# GL3520_4_Ports.net
KiCad netlist of a schematic drawn in Altium Designer
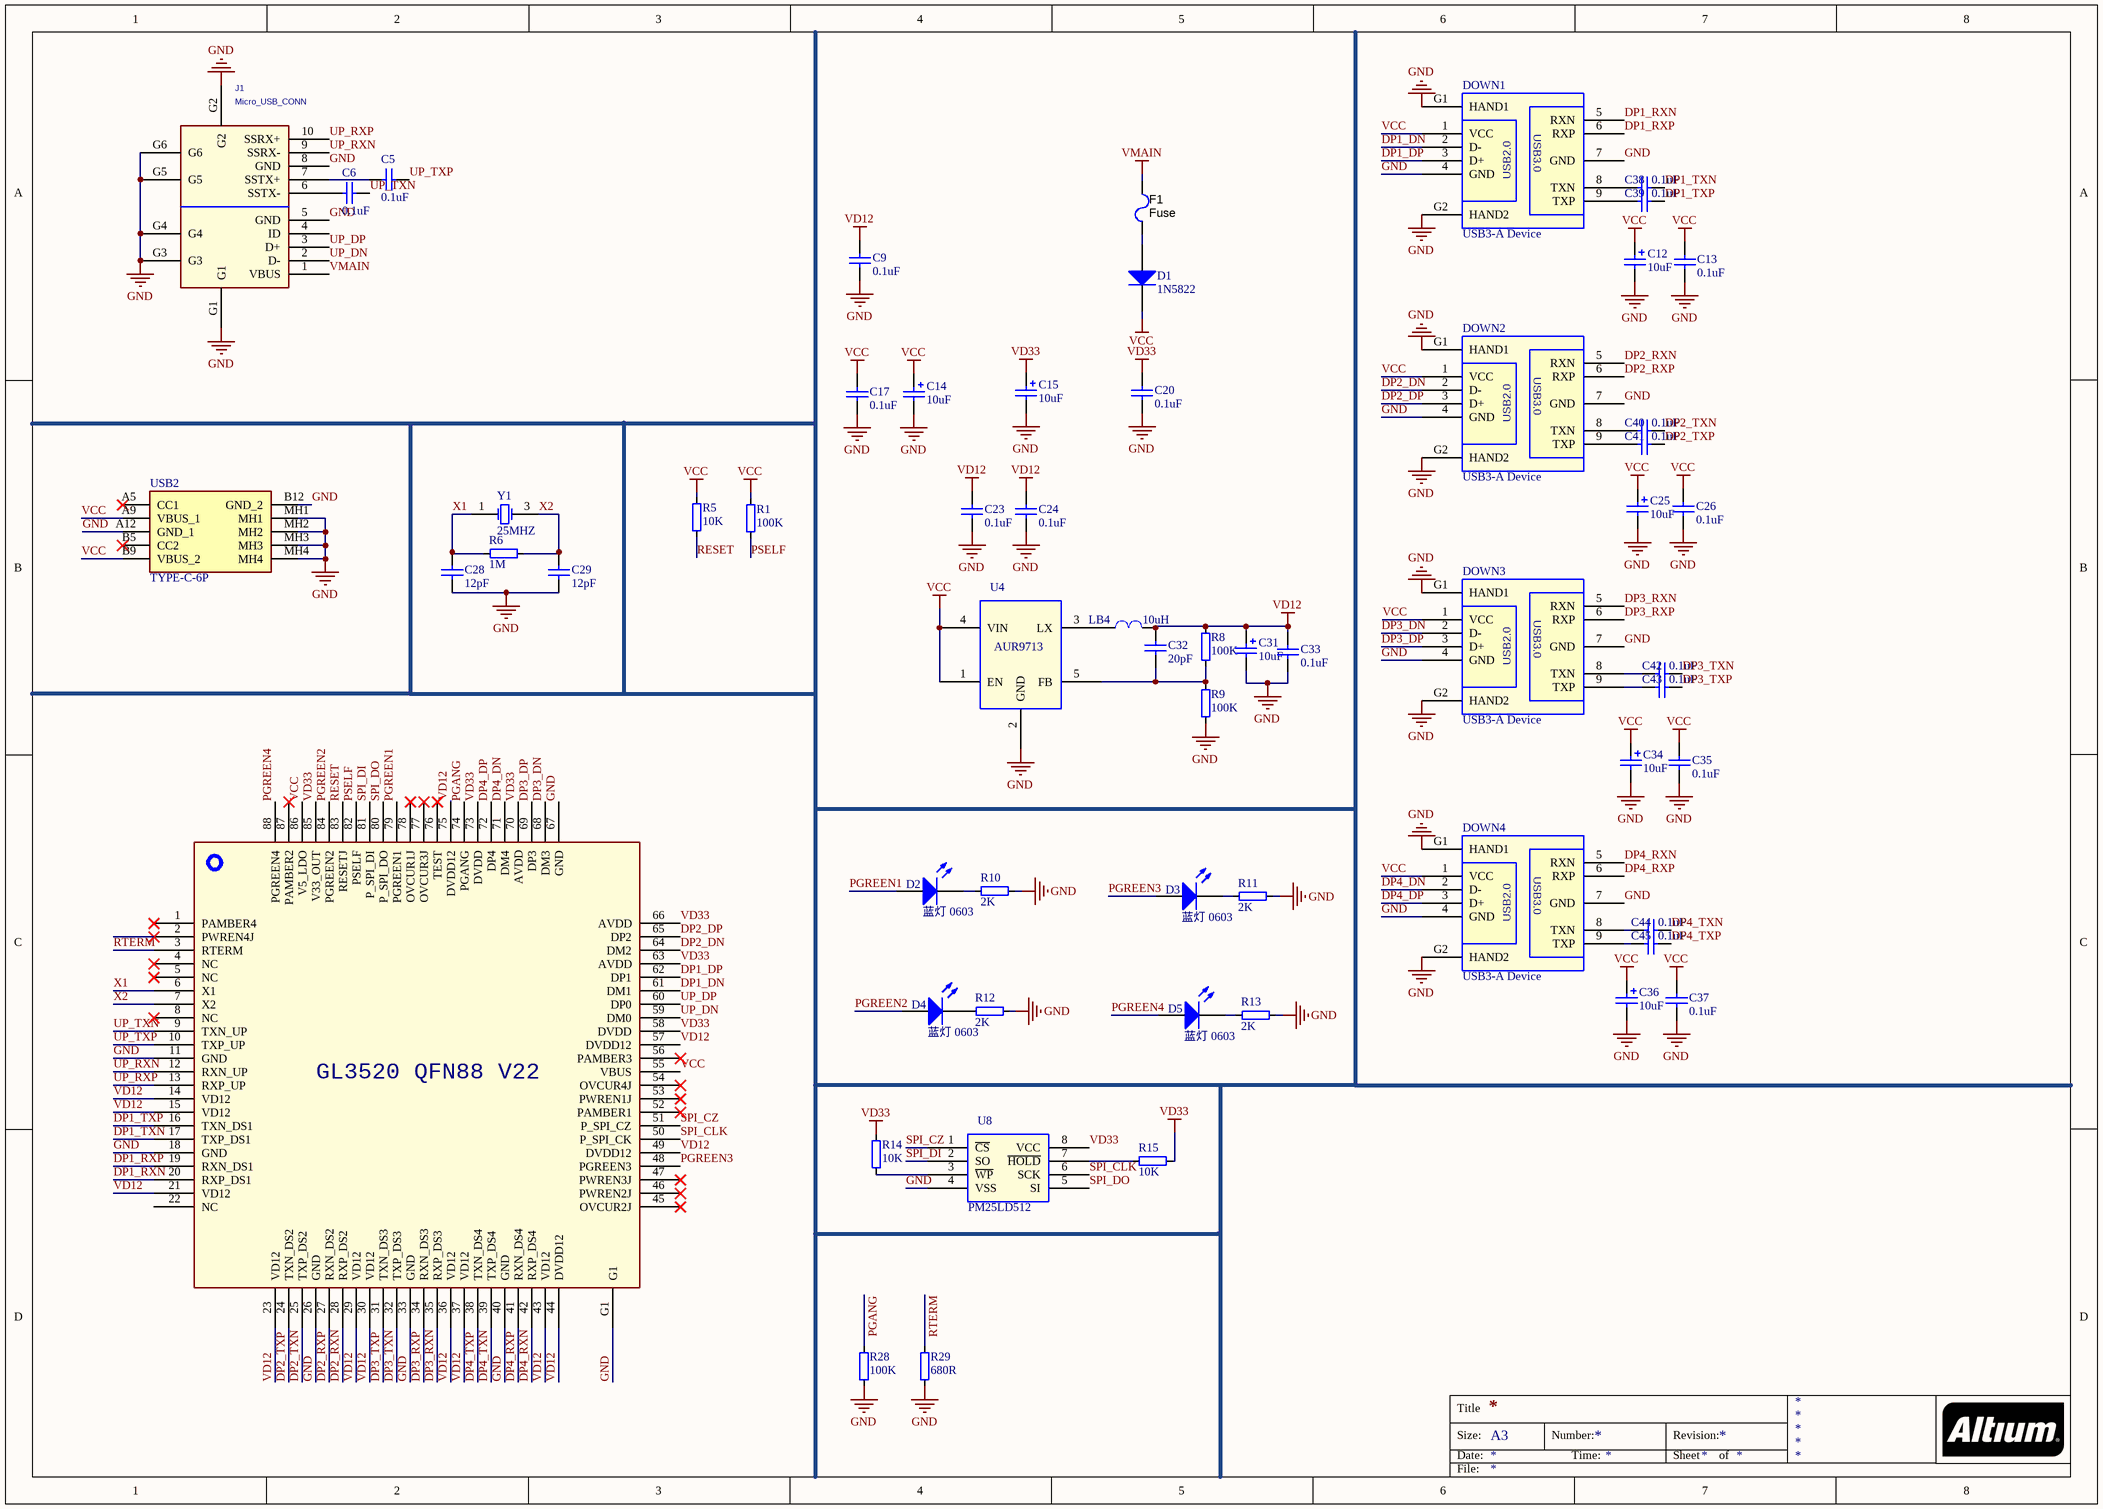
[diagram p0: GL3520 4 Ports.SchDoc]

(export (version "E")
  (design (tool "Eeschema 10.0.6"))
  (components
    (comp (ref "C5")
      (value "0.1uF")
      (footprint "C 0603_L")
      (description "贴片电容")
      (libsource (lib "嘉立创") (part "0603 2.2uF (225) 10% 16V"))
    )
    (comp (ref "C6")
      (value "0.1uF")
      (footprint "C 0603_L")
      (description "贴片电容")
      (libsource (lib "嘉立创") (part "0603 2.2uF (225) 10% 16V"))
    )
    (comp (ref "C9")
      (value "0.1uF")
      (footprint "C 0603_L")
      (description "贴片电容")
      (libsource (lib "嘉立创") (part "0603 2.2uF (225) 10% 16V"))
    )
    (comp (ref "C12")
      (value "10uF")
      (footprint "CASE-A_3216")
      (description "钽电容")
      (libsource (lib "嘉立创") (part "3216 10uF (106) 10% 16V"))
    )
    (comp (ref "C13")
      (value "0.1uF")
      (footprint "C 0603_L")
      (description "贴片电容")
      (libsource (lib "嘉立创") (part "0603 2.2uF (225) 10% 16V"))
    )
    (comp (ref "C14")
      (value "10uF")
      (footprint "CASE-A_3216")
      (description "钽电容1206")
      (libsource (lib "嘉立创") (part "3216 10uF (106) 10% 16V"))
    )
    (comp (ref "C15")
      (value "10uF")
      (footprint "CASE-A_3216")
      (description "钽电容1206")
      (libsource (lib "嘉立创") (part "3216 10uF (106) 10% 16V"))
    )
    (comp (ref "C17")
      (value "0.1uF")
      (footprint "C 0603_L")
      (description "贴片电容")
      (libsource (lib "嘉立创") (part "0603 2.2uF (225) 10% 16V"))
    )
    (comp (ref "C20")
      (value "0.1uF")
      (footprint "C 0603_L")
      (description "贴片电容")
      (libsource (lib "嘉立创") (part "0603 2.2uF (225) 10% 16V"))
    )
    (comp (ref "C23")
      (value "0.1uF")
      (footprint "C 0603_L")
      (description "贴片电容")
      (libsource (lib "嘉立创") (part "0603 2.2uF (225) 10% 16V"))
    )
    (comp (ref "C24")
      (value "0.1uF")
      (footprint "C 0603_L")
      (description "贴片电容")
      (libsource (lib "嘉立创") (part "0603 2.2uF (225) 10% 16V"))
    )
    (comp (ref "C25")
      (value "10uF")
      (footprint "CASE-A_3216")
      (description "钽电容")
      (libsource (lib "嘉立创") (part "3216 10uF (106) 10% 16V"))
    )
    (comp (ref "C26")
      (value "0.1uF")
      (footprint "C 0603_L")
      (description "贴片电容")
      (libsource (lib "嘉立创") (part "0603 2.2uF (225) 10% 16V"))
    )
    (comp (ref "C28")
      (value "12pF")
      (footprint "C 0603_L")
      (description "贴片电容")
      (libsource (lib "嘉立创") (part "0603 2.2uF (225) 10% 16V"))
    )
    (comp (ref "C29")
      (value "12pF")
      (footprint "C 0603_L")
      (description "贴片电容")
      (libsource (lib "嘉立创") (part "0603 2.2uF (225) 10% 16V"))
    )
    (comp (ref "C31")
      (value "10uF")
      (footprint "CASE-A_3216")
      (description "钽电容")
      (libsource (lib "嘉立创") (part "3216 10uF (106) 10% 16V"))
    )
    (comp (ref "C32")
      (value "20pF")
      (footprint "C 0603_L")
      (description "贴片电容")
      (libsource (lib "嘉立创") (part "0603 2.2uF (225) 10% 16V"))
    )
    (comp (ref "C33")
      (value "0.1uF")
      (footprint "C 0603_L")
      (description "贴片电容")
      (libsource (lib "嘉立创") (part "0603 2.2uF (225) 10% 16V"))
    )
    (comp (ref "C34")
      (value "10uF")
      (footprint "CASE-A_3216")
      (description "钽电容")
      (libsource (lib "嘉立创") (part "3216 10uF (106) 10% 16V"))
    )
    (comp (ref "C35")
      (value "0.1uF")
      (footprint "C 0603_L")
      (description "贴片电容")
      (libsource (lib "嘉立创") (part "0603 2.2uF (225) 10% 16V"))
    )
    (comp (ref "C36")
      (value "10uF")
      (footprint "CASE-A_3216")
      (description "钽电容")
      (libsource (lib "嘉立创") (part "3216 10uF (106) 10% 16V"))
    )
    (comp (ref "C37")
      (value "0.1uF")
      (footprint "C 0603_L")
      (description "贴片电容")
      (libsource (lib "嘉立创") (part "0603 2.2uF (225) 10% 16V"))
    )
    (comp (ref "C38")
      (value "0.1uF")
      (footprint "C 0603_L")
      (description "贴片电容")
      (libsource (lib "嘉立创") (part "0603 2.2uF (225) 10% 16V"))
    )
    (comp (ref "C39")
      (value "0.1uF")
      (footprint "C 0603_L")
      (description "贴片电容")
      (libsource (lib "嘉立创") (part "0603 2.2uF (225) 10% 16V"))
    )
    (comp (ref "C40")
      (value "0.1uF")
      (footprint "C 0603_L")
      (description "贴片电容")
      (libsource (lib "嘉立创") (part "0603 2.2uF (225) 10% 16V"))
    )
    (comp (ref "C41")
      (value "0.1uF")
      (footprint "C 0603_L")
      (description "贴片电容")
      (libsource (lib "嘉立创") (part "0603 2.2uF (225) 10% 16V"))
    )
    (comp (ref "C42")
      (value "0.1uF")
      (footprint "C 0603_L")
      (description "贴片电容")
      (libsource (lib "嘉立创") (part "0603 2.2uF (225) 10% 16V"))
    )
    (comp (ref "C43")
      (value "0.1uF")
      (footprint "C 0603_L")
      (description "贴片电容")
      (libsource (lib "嘉立创") (part "0603 2.2uF (225) 10% 16V"))
    )
    (comp (ref "C44")
      (value "0.1uF")
      (footprint "C 0603_L")
      (description "贴片电容")
      (libsource (lib "嘉立创") (part "0603 2.2uF (225) 10% 16V"))
    )
    (comp (ref "C45")
      (value "0.1uF")
      (footprint "C 0603_L")
      (description "贴片电容")
      (libsource (lib "嘉立创") (part "0603 2.2uF (225) 10% 16V"))
    )
    (comp (ref "D1")
      (value "1N5822")
      (footprint "SMA")
      (description "3 Amp General Purpose Rectifier")
      (fields (field (name "PUBLISHER") "Altium Limited"))
      (libsource (lib "Miscellaneous Devices") (part "Diode 1N5400"))
    )
    (comp (ref "D2")
      (value "蓝灯 0603")
      (footprint "0603_LED_S1")
      (description "发光二极管")
      (libsource (lib "嘉立创") (part "0603 蓝灯"))
    )
    (comp (ref "D3")
      (value "蓝灯 0603")
      (footprint "0603_LED_S1")
      (description "发光二极管")
      (libsource (lib "嘉立创") (part "0603 蓝灯"))
    )
    (comp (ref "D4")
      (value "蓝灯 0603")
      (footprint "0603_LED_S1")
      (description "发光二极管")
      (libsource (lib "嘉立创") (part "0603 蓝灯"))
    )
    (comp (ref "D5")
      (value "蓝灯 0603")
      (footprint "0603_LED_S1")
      (description "发光二极管")
      (libsource (lib "嘉立创") (part "0603 蓝灯"))
    )
    (comp (ref "DOWN1")
      (value "USB3-A Device")
      (footprint "USB3.0-2 - duplicate")
      (libsource (lib "*") (part "USB3-A_5"))
    )
    (comp (ref "DOWN2")
      (value "USB3-A Device")
      (footprint "USB3.0-2 - duplicate")
      (libsource (lib "*") (part "USB3-A_5"))
    )
    (comp (ref "DOWN3")
      (value "USB3-A Device")
      (footprint "USB3.0-2 - duplicate")
      (libsource (lib "*") (part "USB3-A_5"))
    )
    (comp (ref "DOWN4")
      (value "USB3-A Device")
      (footprint "USB3.0-2 - duplicate")
      (libsource (lib "*") (part "USB3-A_5"))
    )
    (comp (ref "F1")
      (value "Fuse")
      (footprint "FU 1206")
      (fields
        (field (name "PARTNUMBER") "NANOSMDC020F-2")
        (field (name "MANUFACTURER") "TE Connectivity")
        (field (name "PUBLISHER") "Texas Instruments")
        (field (name "SYMBOLCREATOR") "a0412235")
      )
      (libsource (lib "TUSB8041_USB_3.0_Hub") (part "Fuse"))
    )
    (comp (ref "J1") (value "Micro_USB_CONN") (libsource (lib "*") (part "USB-UEB11123-2JK1-4H_0")))
    (comp (ref "LB4") (value "10uH") (footprint "CD43") (libsource (lib "*") (part "L-0603")))
    (comp (ref "R1") (value "100K") (footprint "R 0603_L") (libsource (lib "Jlink OB") (part "RES")))
    (comp (ref "R5") (value "10K") (footprint "R 0603_L") (libsource (lib "Jlink OB") (part "RES")))
    (comp (ref "R6") (value "1M") (footprint "R 0603_L") (libsource (lib "Jlink OB") (part "RES")))
    (comp (ref "R8") (value "100K") (footprint "R 0603_L") (libsource (lib "Jlink OB") (part "RES")))
    (comp (ref "R9") (value "100K") (footprint "R 0603_L") (libsource (lib "Jlink OB") (part "RES")))
    (comp (ref "R10") (value "2K") (footprint "R 0603_L") (libsource (lib "Jlink OB") (part "RES")))
    (comp (ref "R11") (value "2K") (footprint "R 0603_L") (libsource (lib "Jlink OB") (part "RES")))
    (comp (ref "R12") (value "2K") (footprint "R 0603_L") (libsource (lib "Jlink OB") (part "RES")))
    (comp (ref "R13") (value "2K") (footprint "R 0603_L") (libsource (lib "Jlink OB") (part "RES")))
    (comp (ref "R14") (value "10K") (footprint "R 0603_L") (libsource (lib "Jlink OB") (part "RES")))
    (comp (ref "R15") (value "10K") (footprint "R 0603_L") (libsource (lib "Jlink OB") (part "RES")))
    (comp (ref "R28") (value "100K") (footprint "R 0603_L") (libsource (lib "Jlink OB") (part "RES")))
    (comp (ref "R29") (value "680R") (footprint "R 0603_L") (libsource (lib "Jlink OB") (part "RES")))
    (comp (ref "U4") (value "AUR9713") (footprint "SOT23-5L") (libsource (lib "*") (part "AUR9705_3")))
    (comp (ref "U6")
      (value "GL3520_QFN88_V094-1_22")
      (footprint "QFN88")
      (libsource (lib "GL3520 4 Ports") (part "GL3520_QFN88_V094-1_22"))
    )
    (comp (ref "U8") (value "PM25LD512") (footprint "SOP8_M") (libsource (lib "*") (part "CAT25C128/256")))
    (comp (ref "USB2")
      (value "TYPE-C-6P")
      (footprint "TYPE-C-SMD_TYPE-C-31-M-16 - duplicate")
      (description "Connector")
      (fields (field (name "MANUFACTURER_PART_NUMBER") "TYPE-C-31-M-17"))
      (libsource (lib "SamacSys") (part "TYPE-C-31-M-17"))
    )
    (comp (ref "Y1")
      (value "25MHZ")
      (footprint "OSC 3225-4P")
      (description "贴片晶振")
      (libsource (lib "嘉立创") (part "SMD-3225_4P  25MHZ 12PF 10PPM"))
    )
  )
  (nets
    (net (code "1") (name "/DP1_DN") (class "Default")
      (node (ref "DOWN1") (pin "2") (pinfunction "D-_2") (pintype "passive"))
      (node (ref "U6") (pin "61") (pinfunction "DM1_61") (pintype "passive"))
    )
    (net (code "2") (name "/DP1_DP") (class "Default")
      (node (ref "DOWN1") (pin "3") (pinfunction "D+_3") (pintype "passive"))
      (node (ref "U6") (pin "62") (pinfunction "DP1_62") (pintype "passive"))
    )
    (net (code "3") (name "/DP1_RXN") (class "Default")
      (node (ref "DOWN1") (pin "5") (pinfunction "RXN_5") (pintype "passive"))
      (node (ref "U6") (pin "20") (pinfunction "RXP_DS1_20") (pintype "passive"))
    )
    (net (code "4") (name "/DP1_RXP") (class "Default")
      (node (ref "DOWN1") (pin "6") (pinfunction "RXP_6") (pintype "passive"))
      (node (ref "U6") (pin "19") (pinfunction "RXN_DS1_19") (pintype "passive"))
    )
    (net (code "5") (name "/DP1_TXN") (class "Default")
      (node (ref "C38") (pin "1") (pinfunction "1_1") (pintype "passive"))
      (node (ref "U6") (pin "17") (pinfunction "TXP_DS1_17") (pintype "passive"))
    )
    (net (code "6") (name "/DP1_TXP") (class "Default")
      (node (ref "C39") (pin "1") (pinfunction "1_1") (pintype "passive"))
      (node (ref "U6") (pin "16") (pinfunction "TXN_DS1_16") (pintype "passive"))
    )
    (net (code "7") (name "/DP2_DN") (class "Default")
      (node (ref "DOWN2") (pin "2") (pinfunction "D-_2") (pintype "passive"))
      (node (ref "U6") (pin "64") (pinfunction "DM2_64") (pintype "passive"))
    )
    (net (code "8") (name "/DP2_DP") (class "Default")
      (node (ref "DOWN2") (pin "3") (pinfunction "D+_3") (pintype "passive"))
      (node (ref "U6") (pin "65") (pinfunction "DP2_65") (pintype "passive"))
    )
    (net (code "9") (name "/DP2_RXN") (class "Default")
      (node (ref "DOWN2") (pin "5") (pinfunction "RXN_5") (pintype "passive"))
      (node (ref "U6") (pin "28") (pinfunction "RXP_DS2_28") (pintype "passive"))
    )
    (net (code "10") (name "/DP2_RXP") (class "Default")
      (node (ref "DOWN2") (pin "6") (pinfunction "RXP_6") (pintype "passive"))
      (node (ref "U6") (pin "27") (pinfunction "RXN_DS2_27") (pintype "passive"))
    )
    (net (code "11") (name "/DP2_TXN") (class "Default")
      (node (ref "C40") (pin "1") (pinfunction "1_1") (pintype "passive"))
      (node (ref "U6") (pin "25") (pinfunction "TXP_DS2_25") (pintype "passive"))
    )
    (net (code "12") (name "/DP2_TXP") (class "Default")
      (node (ref "C41") (pin "1") (pinfunction "1_1") (pintype "passive"))
      (node (ref "U6") (pin "24") (pinfunction "TXN_DS2_24") (pintype "passive"))
    )
    (net (code "13") (name "/DP3_DN") (class "Default")
      (node (ref "DOWN3") (pin "2") (pinfunction "D-_2") (pintype "passive"))
      (node (ref "U6") (pin "68") (pinfunction "DM3_68") (pintype "passive"))
    )
    (net (code "14") (name "/DP3_DP") (class "Default")
      (node (ref "DOWN3") (pin "3") (pinfunction "D+_3") (pintype "passive"))
      (node (ref "U6") (pin "69") (pinfunction "DP3_69") (pintype "passive"))
    )
    (net (code "15") (name "/DP3_RXN") (class "Default")
      (node (ref "DOWN3") (pin "5") (pinfunction "RXN_5") (pintype "passive"))
      (node (ref "U6") (pin "35") (pinfunction "RXP_DS3_35") (pintype "passive"))
    )
    (net (code "16") (name "/DP3_RXP") (class "Default")
      (node (ref "DOWN3") (pin "6") (pinfunction "RXP_6") (pintype "passive"))
      (node (ref "U6") (pin "34") (pinfunction "RXN_DS3_34") (pintype "passive"))
    )
    (net (code "17") (name "/DP3_TXN") (class "Default")
      (node (ref "C42") (pin "1") (pinfunction "1_1") (pintype "passive"))
      (node (ref "U6") (pin "32") (pinfunction "TXP_DS3_32") (pintype "passive"))
    )
    (net (code "18") (name "/DP3_TXP") (class "Default")
      (node (ref "C43") (pin "1") (pinfunction "1_1") (pintype "passive"))
      (node (ref "U6") (pin "31") (pinfunction "TXN_DS3_31") (pintype "passive"))
    )
    (net (code "19") (name "/DP4_DN") (class "Default")
      (node (ref "DOWN4") (pin "2") (pinfunction "D-_2") (pintype "passive"))
      (node (ref "U6") (pin "71") (pinfunction "DM4_71") (pintype "passive"))
    )
    (net (code "20") (name "/DP4_DP") (class "Default")
      (node (ref "DOWN4") (pin "3") (pinfunction "D+_3") (pintype "passive"))
      (node (ref "U6") (pin "72") (pinfunction "DP4_72") (pintype "passive"))
    )
    (net (code "21") (name "/DP4_RXN") (class "Default")
      (node (ref "DOWN4") (pin "5") (pinfunction "RXN_5") (pintype "passive"))
      (node (ref "U6") (pin "42") (pinfunction "RXP_DS4_42") (pintype "passive"))
    )
    (net (code "22") (name "/DP4_RXP") (class "Default")
      (node (ref "DOWN4") (pin "6") (pinfunction "RXP_6") (pintype "passive"))
      (node (ref "U6") (pin "41") (pinfunction "RXN_DS4_41") (pintype "passive"))
    )
    (net (code "23") (name "/DP4_TXN") (class "Default")
      (node (ref "C44") (pin "1") (pinfunction "1_1") (pintype "passive"))
      (node (ref "U6") (pin "39") (pinfunction "TXP_DS4_39") (pintype "passive"))
    )
    (net (code "24") (name "/DP4_TXP") (class "Default")
      (node (ref "C45") (pin "1") (pinfunction "1_1") (pintype "passive"))
      (node (ref "U6") (pin "38") (pinfunction "TXN_DS4_38") (pintype "passive"))
    )
    (net (code "25") (name "/PGANG") (class "Default")
      (node (ref "R28") (pin "1") (pinfunction "1_1") (pintype "passive"))
      (node (ref "U6") (pin "74") (pinfunction "PGANG_74") (pintype "passive"))
    )
    (net (code "26") (name "/PGREEN1") (class "Default")
      (node (ref "D2") (pin "A") (pinfunction "A_A") (pintype "passive"))
      (node (ref "U6") (pin "79") (pinfunction "PGREEN1_79") (pintype "passive"))
    )
    (net (code "27") (name "/PGREEN2") (class "Default")
      (node (ref "D4") (pin "A") (pinfunction "A_A") (pintype "passive"))
      (node (ref "U6") (pin "84") (pinfunction "PGREEN2_84") (pintype "passive"))
    )
    (net (code "28") (name "/PGREEN3") (class "Default")
      (node (ref "D3") (pin "A") (pinfunction "A_A") (pintype "passive"))
      (node (ref "U6") (pin "48") (pinfunction "PGREEN3_48") (pintype "passive"))
    )
    (net (code "29") (name "/PGREEN4") (class "Default")
      (node (ref "D5") (pin "A") (pinfunction "A_A") (pintype "passive"))
      (node (ref "U6") (pin "88") (pinfunction "PGREEN4_88") (pintype "passive"))
    )
    (net (code "30") (name "/PSELF") (class "Default")
      (node (ref "R1") (pin "2") (pinfunction "2_2") (pintype "passive"))
      (node (ref "U6") (pin "82") (pinfunction "PSELF_82") (pintype "passive"))
    )
    (net (code "31") (name "/RESET") (class "Default")
      (node (ref "R5") (pin "1") (pinfunction "1_1") (pintype "passive"))
      (node (ref "U6") (pin "83") (pinfunction "RESETJ_83") (pintype "passive"))
    )
    (net (code "32") (name "/RTERM") (class "Default")
      (node (ref "R29") (pin "1") (pinfunction "1_1") (pintype "passive"))
      (node (ref "U6") (pin "3") (pinfunction "RTERM_3") (pintype "passive"))
    )
    (net (code "33") (name "/SPI_CLK") (class "Default")
      (node (ref "U6") (pin "50") (pinfunction "P_SPI_CK_50") (pintype "passive"))
      (node (ref "U8") (pin "6") (pinfunction "SCK_6") (pintype "passive"))
    )
    (net (code "34") (name "/SPI_CZ") (class "Default")
      (node (ref "U6") (pin "51") (pinfunction "P_SPI_CZ_51") (pintype "passive"))
      (node (ref "U8") (pin "1") (pinfunction "~{CS}_1") (pintype "passive"))
    )
    (net (code "35") (name "/SPI_DI") (class "Default")
      (node (ref "U6") (pin "81") (pinfunction "P_SPI_DI_81") (pintype "passive"))
      (node (ref "U8") (pin "2") (pinfunction "SO_2") (pintype "passive"))
    )
    (net (code "36") (name "/SPI_DO") (class "Default")
      (node (ref "U6") (pin "80") (pinfunction "P_SPI_DO_80") (pintype "passive"))
      (node (ref "U8") (pin "5") (pinfunction "SI_5") (pintype "passive"))
    )
    (net (code "37") (name "/UP_DN") (class "Default")
      (node (ref "J1") (pin "2") (pinfunction "D-_2") (pintype "passive"))
      (node (ref "U6") (pin "59") (pinfunction "DM0_59") (pintype "passive"))
    )
    (net (code "38") (name "/UP_DP") (class "Default")
      (node (ref "J1") (pin "3") (pinfunction "D+_3") (pintype "passive"))
      (node (ref "U6") (pin "60") (pinfunction "DP0_60") (pintype "passive"))
    )
    (net (code "39") (name "/UP_RXN") (class "Default")
      (node (ref "J1") (pin "9") (pinfunction "SSRX-_9") (pintype "passive"))
      (node (ref "U6") (pin "12") (pinfunction "RXN_UP_12") (pintype "passive"))
    )
    (net (code "40") (name "/UP_RXP") (class "Default")
      (node (ref "J1") (pin "10") (pinfunction "SSRX+_10") (pintype "passive"))
      (node (ref "U6") (pin "13") (pinfunction "RXP_UP_13") (pintype "passive"))
    )
    (net (code "41") (name "/UP_TXN") (class "Default")
      (node (ref "C6") (pin "1") (pinfunction "1_1") (pintype "passive"))
      (node (ref "U6") (pin "9") (pinfunction "TXN_UP_9") (pintype "passive"))
    )
    (net (code "42") (name "/UP_TXP") (class "Default")
      (node (ref "C5") (pin "1") (pinfunction "1_1") (pintype "passive"))
      (node (ref "U6") (pin "10") (pinfunction "TXP_UP_10") (pintype "passive"))
    )
    (net (code "43") (name "/X1") (class "Default")
      (node (ref "C28") (pin "2") (pinfunction "2_2") (pintype "passive"))
      (node (ref "R6") (pin "1") (pinfunction "1_1") (pintype "passive"))
      (node (ref "U6") (pin "6") (pinfunction "X1_6") (pintype "passive"))
      (node (ref "Y1") (pin "1") (pinfunction "OSC1_1") (pintype "passive"))
    )
    (net (code "44") (name "/X2") (class "Default")
      (node (ref "C29") (pin "2") (pinfunction "2_2") (pintype "passive"))
      (node (ref "R6") (pin "2") (pinfunction "2_2") (pintype "passive"))
      (node (ref "U6") (pin "7") (pinfunction "X2_7") (pintype "passive"))
      (node (ref "Y1") (pin "3") (pinfunction "OSC2_3") (pintype "passive"))
    )
    (net (code "45") (name "GND") (class "Default")
      (node (ref "C12") (pin "2") (pinfunction "2_2") (pintype "passive"))
      (node (ref "C13") (pin "1") (pinfunction "1_1") (pintype "passive"))
      (node (ref "C14") (pin "2") (pinfunction "2_2") (pintype "passive"))
      (node (ref "C15") (pin "2") (pinfunction "2_2") (pintype "passive"))
      (node (ref "C17") (pin "1") (pinfunction "1_1") (pintype "passive"))
      (node (ref "C20") (pin "1") (pinfunction "1_1") (pintype "passive"))
      (node (ref "C23") (pin "1") (pinfunction "1_1") (pintype "passive"))
      (node (ref "C24") (pin "1") (pinfunction "1_1") (pintype "passive"))
      (node (ref "C25") (pin "2") (pinfunction "2_2") (pintype "passive"))
      (node (ref "C26") (pin "1") (pinfunction "1_1") (pintype "passive"))
      (node (ref "C28") (pin "1") (pinfunction "1_1") (pintype "passive"))
      (node (ref "C29") (pin "1") (pinfunction "1_1") (pintype "passive"))
      (node (ref "C31") (pin "2") (pinfunction "2_2") (pintype "passive"))
      (node (ref "C33") (pin "1") (pinfunction "1_1") (pintype "passive"))
      (node (ref "C34") (pin "2") (pinfunction "2_2") (pintype "passive"))
      (node (ref "C35") (pin "1") (pinfunction "1_1") (pintype "passive"))
      (node (ref "C36") (pin "2") (pinfunction "2_2") (pintype "passive"))
      (node (ref "C37") (pin "1") (pinfunction "1_1") (pintype "passive"))
      (node (ref "C9") (pin "1") (pinfunction "1_1") (pintype "passive"))
      (node (ref "DOWN1") (pin "4") (pinfunction "GND_4") (pintype "power_in"))
      (node (ref "DOWN1") (pin "7") (pinfunction "GND_7") (pintype "power_in"))
      (node (ref "DOWN1") (pin "G1") (pinfunction "HAND1_G1") (pintype "passive"))
      (node (ref "DOWN1") (pin "G2") (pinfunction "HAND2_G2") (pintype "passive"))
      (node (ref "DOWN2") (pin "4") (pinfunction "GND_4") (pintype "power_in"))
      (node (ref "DOWN2") (pin "7") (pinfunction "GND_7") (pintype "power_in"))
      (node (ref "DOWN2") (pin "G1") (pinfunction "HAND1_G1") (pintype "passive"))
      (node (ref "DOWN2") (pin "G2") (pinfunction "HAND2_G2") (pintype "passive"))
      (node (ref "DOWN3") (pin "4") (pinfunction "GND_4") (pintype "power_in"))
      (node (ref "DOWN3") (pin "7") (pinfunction "GND_7") (pintype "power_in"))
      (node (ref "DOWN3") (pin "G1") (pinfunction "HAND1_G1") (pintype "passive"))
      (node (ref "DOWN3") (pin "G2") (pinfunction "HAND2_G2") (pintype "passive"))
      (node (ref "DOWN4") (pin "4") (pinfunction "GND_4") (pintype "power_in"))
      (node (ref "DOWN4") (pin "7") (pinfunction "GND_7") (pintype "power_in"))
      (node (ref "DOWN4") (pin "G1") (pinfunction "HAND1_G1") (pintype "passive"))
      (node (ref "DOWN4") (pin "G2") (pinfunction "HAND2_G2") (pintype "passive"))
      (node (ref "J1") (pin "5") (pinfunction "GND_5") (pintype "power_in"))
      (node (ref "J1") (pin "8") (pinfunction "GND_8") (pintype "power_in"))
      (node (ref "J1") (pin "G1") (pinfunction "G1_G1") (pintype "passive"))
      (node (ref "J1") (pin "G2") (pinfunction "G2_G2") (pintype "passive"))
      (node (ref "J1") (pin "G3") (pinfunction "G3_G3") (pintype "passive"))
      (node (ref "J1") (pin "G4") (pinfunction "G4_G4") (pintype "passive"))
      (node (ref "J1") (pin "G5") (pinfunction "G5_G5") (pintype "passive"))
      (node (ref "J1") (pin "G6") (pinfunction "G6_G6") (pintype "passive"))
      (node (ref "R10") (pin "1") (pinfunction "1_1") (pintype "passive"))
      (node (ref "R11") (pin "1") (pinfunction "1_1") (pintype "passive"))
      (node (ref "R12") (pin "1") (pinfunction "1_1") (pintype "passive"))
      (node (ref "R13") (pin "1") (pinfunction "1_1") (pintype "passive"))
      (node (ref "R28") (pin "2") (pinfunction "2_2") (pintype "passive"))
      (node (ref "R29") (pin "2") (pinfunction "2_2") (pintype "passive"))
      (node (ref "R9") (pin "2") (pinfunction "2_2") (pintype "passive"))
      (node (ref "U4") (pin "2") (pinfunction "GND_2") (pintype "passive"))
      (node (ref "U6") (pin "11") (pinfunction "GND_11") (pintype "passive"))
      (node (ref "U6") (pin "18") (pinfunction "GND_18") (pintype "passive"))
      (node (ref "U6") (pin "26") (pinfunction "GND_26") (pintype "passive"))
      (node (ref "U6") (pin "33") (pinfunction "GND_33") (pintype "passive"))
      (node (ref "U6") (pin "40") (pinfunction "GND_40") (pintype "passive"))
      (node (ref "U6") (pin "67") (pinfunction "GND_67") (pintype "passive"))
      (node (ref "U6") (pin "G1") (pinfunction "G1_G1") (pintype "passive"))
      (node (ref "U8") (pin "4") (pinfunction "VSS_4") (pintype "passive"))
      (node (ref "USB2") (pin "A12") (pinfunction "GND_1_A12") (pintype "passive"))
      (node (ref "USB2") (pin "B12") (pinfunction "GND_2_B12") (pintype "passive"))
      (node (ref "USB2") (pin "MH1") (pinfunction "MH1_MH1") (pintype "passive"))
      (node (ref "USB2") (pin "MH2") (pinfunction "MH2_MH2") (pintype "passive"))
      (node (ref "USB2") (pin "MH3") (pinfunction "MH3_MH3") (pintype "passive"))
      (node (ref "USB2") (pin "MH4") (pinfunction "MH4_MH4") (pintype "passive"))
    )
    (net (code "46") (name "Net-(D1-A)") (class "Default")
      (node (ref "D1") (pin "1") (pinfunction "A_1") (pintype "passive"))
      (node (ref "F1") (pin "2") (pinfunction "2_2") (pintype "passive"))
    )
    (net (code "47") (name "Net-(D2-PadK)") (class "Default")
      (node (ref "D2") (pin "K") (pinfunction "K_K") (pintype "passive"))
      (node (ref "R10") (pin "2") (pinfunction "2_2") (pintype "passive"))
    )
    (net (code "48") (name "Net-(D3-PadK)") (class "Default")
      (node (ref "D3") (pin "K") (pinfunction "K_K") (pintype "passive"))
      (node (ref "R11") (pin "2") (pinfunction "2_2") (pintype "passive"))
    )
    (net (code "49") (name "Net-(D4-PadK)") (class "Default")
      (node (ref "D4") (pin "K") (pinfunction "K_K") (pintype "passive"))
      (node (ref "R12") (pin "2") (pinfunction "2_2") (pintype "passive"))
    )
    (net (code "50") (name "Net-(D5-PadK)") (class "Default")
      (node (ref "D5") (pin "K") (pinfunction "K_K") (pintype "passive"))
      (node (ref "R13") (pin "2") (pinfunction "2_2") (pintype "passive"))
    )
    (net (code "51") (name "Net-(DOWN1-TXN)") (class "Default")
      (node (ref "C38") (pin "2") (pinfunction "2_2") (pintype "passive"))
      (node (ref "DOWN1") (pin "8") (pinfunction "TXN_8") (pintype "passive"))
    )
    (net (code "52") (name "Net-(DOWN1-TXP)") (class "Default")
      (node (ref "C39") (pin "2") (pinfunction "2_2") (pintype "passive"))
      (node (ref "DOWN1") (pin "9") (pinfunction "TXP_9") (pintype "passive"))
    )
    (net (code "53") (name "Net-(DOWN2-TXN)") (class "Default")
      (node (ref "C40") (pin "2") (pinfunction "2_2") (pintype "passive"))
      (node (ref "DOWN2") (pin "8") (pinfunction "TXN_8") (pintype "passive"))
    )
    (net (code "54") (name "Net-(DOWN2-TXP)") (class "Default")
      (node (ref "C41") (pin "2") (pinfunction "2_2") (pintype "passive"))
      (node (ref "DOWN2") (pin "9") (pinfunction "TXP_9") (pintype "passive"))
    )
    (net (code "55") (name "Net-(DOWN3-TXN)") (class "Default")
      (node (ref "C42") (pin "2") (pinfunction "2_2") (pintype "passive"))
      (node (ref "DOWN3") (pin "8") (pinfunction "TXN_8") (pintype "passive"))
    )
    (net (code "56") (name "Net-(DOWN3-TXP)") (class "Default")
      (node (ref "C43") (pin "2") (pinfunction "2_2") (pintype "passive"))
      (node (ref "DOWN3") (pin "9") (pinfunction "TXP_9") (pintype "passive"))
    )
    (net (code "57") (name "Net-(DOWN4-TXN)") (class "Default")
      (node (ref "C44") (pin "2") (pinfunction "2_2") (pintype "passive"))
      (node (ref "DOWN4") (pin "8") (pinfunction "TXN_8") (pintype "passive"))
    )
    (net (code "58") (name "Net-(DOWN4-TXP)") (class "Default")
      (node (ref "C45") (pin "2") (pinfunction "2_2") (pintype "passive"))
      (node (ref "DOWN4") (pin "9") (pinfunction "TXP_9") (pintype "passive"))
    )
    (net (code "59") (name "Net-(J1-SSTX+)") (class "Default")
      (node (ref "C5") (pin "2") (pinfunction "2_2") (pintype "passive"))
      (node (ref "J1") (pin "7") (pinfunction "SSTX+_7") (pintype "passive"))
    )
    (net (code "60") (name "Net-(J1-SSTX-)") (class "Default")
      (node (ref "C6") (pin "2") (pinfunction "2_2") (pintype "passive"))
      (node (ref "J1") (pin "6") (pinfunction "SSTX-_6") (pintype "passive"))
    )
    (net (code "61") (name "Net-(U4-FB)") (class "Default")
      (node (ref "C32") (pin "1") (pinfunction "1_1") (pintype "passive"))
      (node (ref "R8") (pin "2") (pinfunction "2_2") (pintype "passive"))
      (node (ref "R9") (pin "1") (pinfunction "1_1") (pintype "passive"))
      (node (ref "U4") (pin "5") (pinfunction "FB_5") (pintype "passive"))
    )
    (net (code "62") (name "Net-(U4-LX)") (class "Default")
      (node (ref "LB4") (pin "1") (pinfunction "1_1") (pintype "passive"))
      (node (ref "U4") (pin "3") (pinfunction "LX_3") (pintype "passive"))
    )
    (net (code "63") (name "Net-(U8-~{HOLD})") (class "Default")
      (node (ref "R15") (pin "1") (pinfunction "1_1") (pintype "passive"))
      (node (ref "U8") (pin "7") (pinfunction "~{HOLD}_7") (pintype "passive"))
    )
    (net (code "64") (name "Net-(U8-~{WP})") (class "Default")
      (node (ref "R14") (pin "2") (pinfunction "2_2") (pintype "passive"))
      (node (ref "U8") (pin "3") (pinfunction "~{WP}_3") (pintype "passive"))
    )
    (net (code "65") (name "VCC") (class "Default")
      (node (ref "C12") (pin "1") (pinfunction "1_1") (pintype "passive"))
      (node (ref "C13") (pin "2") (pinfunction "2_2") (pintype "passive"))
      (node (ref "C14") (pin "1") (pinfunction "1_1") (pintype "passive"))
      (node (ref "C17") (pin "2") (pinfunction "2_2") (pintype "passive"))
      (node (ref "C25") (pin "1") (pinfunction "1_1") (pintype "passive"))
      (node (ref "C26") (pin "2") (pinfunction "2_2") (pintype "passive"))
      (node (ref "C34") (pin "1") (pinfunction "1_1") (pintype "passive"))
      (node (ref "C35") (pin "2") (pinfunction "2_2") (pintype "passive"))
      (node (ref "C36") (pin "1") (pinfunction "1_1") (pintype "passive"))
      (node (ref "C37") (pin "2") (pinfunction "2_2") (pintype "passive"))
      (node (ref "D1") (pin "2") (pinfunction "K_2") (pintype "passive"))
      (node (ref "DOWN1") (pin "1") (pinfunction "VCC_1") (pintype "power_in"))
      (node (ref "DOWN2") (pin "1") (pinfunction "VCC_1") (pintype "power_in"))
      (node (ref "DOWN3") (pin "1") (pinfunction "VCC_1") (pintype "power_in"))
      (node (ref "DOWN4") (pin "1") (pinfunction "VCC_1") (pintype "power_in"))
      (node (ref "R1") (pin "1") (pinfunction "1_1") (pintype "passive"))
      (node (ref "R5") (pin "2") (pinfunction "2_2") (pintype "passive"))
      (node (ref "U4") (pin "1") (pinfunction "EN_1") (pintype "passive"))
      (node (ref "U4") (pin "4") (pinfunction "VIN_4") (pintype "passive"))
      (node (ref "U6") (pin "55") (pinfunction "VBUS_55") (pintype "passive"))
      (node (ref "U6") (pin "86") (pinfunction "V5_LDO_86") (pintype "passive"))
      (node (ref "USB2") (pin "A9") (pinfunction "VBUS_1_A9") (pintype "passive"))
      (node (ref "USB2") (pin "B9") (pinfunction "VBUS_2_B9") (pintype "passive"))
    )
    (net (code "66") (name "VD12") (class "Default")
      (node (ref "C23") (pin "2") (pinfunction "2_2") (pintype "passive"))
      (node (ref "C24") (pin "2") (pinfunction "2_2") (pintype "passive"))
      (node (ref "C31") (pin "1") (pinfunction "1_1") (pintype "passive"))
      (node (ref "C32") (pin "2") (pinfunction "2_2") (pintype "passive"))
      (node (ref "C33") (pin "2") (pinfunction "2_2") (pintype "passive"))
      (node (ref "C9") (pin "2") (pinfunction "2_2") (pintype "passive"))
      (node (ref "LB4") (pin "2") (pinfunction "2_2") (pintype "passive"))
      (node (ref "R8") (pin "1") (pinfunction "1_1") (pintype "passive"))
      (node (ref "U6") (pin "14") (pinfunction "VD12_14") (pintype "passive"))
      (node (ref "U6") (pin "15") (pinfunction "VD12_15") (pintype "passive"))
      (node (ref "U6") (pin "21") (pinfunction "VD12_21") (pintype "passive"))
      (node (ref "U6") (pin "23") (pinfunction "VD12_23") (pintype "passive"))
      (node (ref "U6") (pin "29") (pinfunction "VD12_29") (pintype "passive"))
      (node (ref "U6") (pin "30") (pinfunction "VD12_30") (pintype "passive"))
      (node (ref "U6") (pin "36") (pinfunction "VD12_36") (pintype "passive"))
      (node (ref "U6") (pin "37") (pinfunction "VD12_37") (pintype "passive"))
      (node (ref "U6") (pin "43") (pinfunction "VD12_43") (pintype "passive"))
      (node (ref "U6") (pin "44") (pinfunction "DVDD12_44") (pintype "passive"))
      (node (ref "U6") (pin "49") (pinfunction "DVDD12_49") (pintype "passive"))
      (node (ref "U6") (pin "57") (pinfunction "DVDD12_57") (pintype "passive"))
      (node (ref "U6") (pin "75") (pinfunction "DVDD12_75") (pintype "passive"))
    )
    (net (code "67") (name "VD33") (class "Default")
      (node (ref "C15") (pin "1") (pinfunction "1_1") (pintype "passive"))
      (node (ref "C20") (pin "2") (pinfunction "2_2") (pintype "passive"))
      (node (ref "R14") (pin "1") (pinfunction "1_1") (pintype "passive"))
      (node (ref "R15") (pin "2") (pinfunction "2_2") (pintype "passive"))
      (node (ref "U6") (pin "58") (pinfunction "DVDD_58") (pintype "passive"))
      (node (ref "U6") (pin "63") (pinfunction "AVDD_63") (pintype "passive"))
      (node (ref "U6") (pin "66") (pinfunction "AVDD_66") (pintype "passive"))
      (node (ref "U6") (pin "70") (pinfunction "AVDD_70") (pintype "passive"))
      (node (ref "U6") (pin "73") (pinfunction "DVDD_73") (pintype "passive"))
      (node (ref "U6") (pin "85") (pinfunction "V33_OUT_85") (pintype "passive"))
      (node (ref "U8") (pin "8") (pinfunction "VCC_8") (pintype "passive"))
    )
    (net (code "68") (name "VMAIN") (class "Default")
      (node (ref "F1") (pin "1") (pinfunction "1_1") (pintype "passive"))
      (node (ref "J1") (pin "1") (pinfunction "VBUS_1") (pintype "passive"))
    )
    (net (code "69") (name "unconnected-(J1-ID-Pad4)") (class "Default")
      (node (ref "J1") (pin "4") (pinfunction "ID_4") (pintype "passive"))
    )
    (net (code "70") (name "unconnected-(U6-NC-Pad4)") (class "Default")
      (node (ref "U6") (pin "4") (pinfunction "NC_4") (pintype "passive+no_connect"))
    )
    (net (code "71") (name "unconnected-(U6-NC-Pad5)") (class "Default")
      (node (ref "U6") (pin "5") (pinfunction "NC_5") (pintype "passive+no_connect"))
    )
    (net (code "72") (name "unconnected-(U6-NC-Pad8)") (class "Default")
      (node (ref "U6") (pin "8") (pinfunction "NC_8") (pintype "passive+no_connect"))
    )
    (net (code "73") (name "unconnected-(U6-NC-Pad22)") (class "Default")
      (node (ref "U6") (pin "22") (pinfunction "NC_22") (pintype "passive"))
    )
    (net (code "74") (name "unconnected-(U6-OVCUR1J-Pad78)") (class "Default")
      (node (ref "U6") (pin "78") (pinfunction "OVCUR1J_78") (pintype "passive+no_connect"))
    )
    (net (code "75") (name "unconnected-(U6-OVCUR2J-Pad45)") (class "Default")
      (node (ref "U6") (pin "45") (pinfunction "OVCUR2J_45") (pintype "passive+no_connect"))
    )
    (net (code "76") (name "unconnected-(U6-OVCUR3J-Pad77)") (class "Default")
      (node (ref "U6") (pin "77") (pinfunction "OVCUR3J_77") (pintype "passive+no_connect"))
    )
    (net (code "77") (name "unconnected-(U6-OVCUR4J-Pad54)") (class "Default")
      (node (ref "U6") (pin "54") (pinfunction "OVCUR4J_54") (pintype "passive+no_connect"))
    )
    (net (code "78") (name "unconnected-(U6-PAMBER1-Pad52)") (class "Default")
      (node (ref "U6") (pin "52") (pinfunction "PAMBER1_52") (pintype "passive+no_connect"))
    )
    (net (code "79") (name "unconnected-(U6-PAMBER2-Pad87)") (class "Default")
      (node (ref "U6") (pin "87") (pinfunction "PAMBER2_87") (pintype "passive+no_connect"))
    )
    (net (code "80") (name "unconnected-(U6-PAMBER3-Pad56)") (class "Default")
      (node (ref "U6") (pin "56") (pinfunction "PAMBER3_56") (pintype "passive+no_connect"))
    )
    (net (code "81") (name "unconnected-(U6-PAMBER4-Pad1)") (class "Default")
      (node (ref "U6") (pin "1") (pinfunction "PAMBER4_1") (pintype "passive+no_connect"))
    )
    (net (code "82") (name "unconnected-(U6-PWREN1J-Pad53)") (class "Default")
      (node (ref "U6") (pin "53") (pinfunction "PWREN1J_53") (pintype "passive+no_connect"))
    )
    (net (code "83") (name "unconnected-(U6-PWREN2J-Pad46)") (class "Default")
      (node (ref "U6") (pin "46") (pinfunction "PWREN2J_46") (pintype "passive+no_connect"))
    )
    (net (code "84") (name "unconnected-(U6-PWREN3J-Pad47)") (class "Default")
      (node (ref "U6") (pin "47") (pinfunction "PWREN3J_47") (pintype "passive+no_connect"))
    )
    (net (code "85") (name "unconnected-(U6-PWREN4J-Pad2)") (class "Default")
      (node (ref "U6") (pin "2") (pinfunction "PWREN4J_2") (pintype "passive+no_connect"))
    )
    (net (code "86") (name "unconnected-(U6-TEST-Pad76)") (class "Default")
      (node (ref "U6") (pin "76") (pinfunction "TEST_76") (pintype "passive+no_connect"))
    )
    (net (code "87") (name "unconnected-(USB2-CC1-PadA5)") (class "Default")
      (node (ref "USB2") (pin "A5") (pinfunction "CC1_A5") (pintype "passive+no_connect"))
    )
    (net (code "88") (name "unconnected-(USB2-CC2-PadB5)") (class "Default")
      (node (ref "USB2") (pin "B5") (pinfunction "CC2_B5") (pintype "passive+no_connect"))
    )
  )
)
